# Chip.net
KiCad netlist of a schematic drawn in Altium Designer
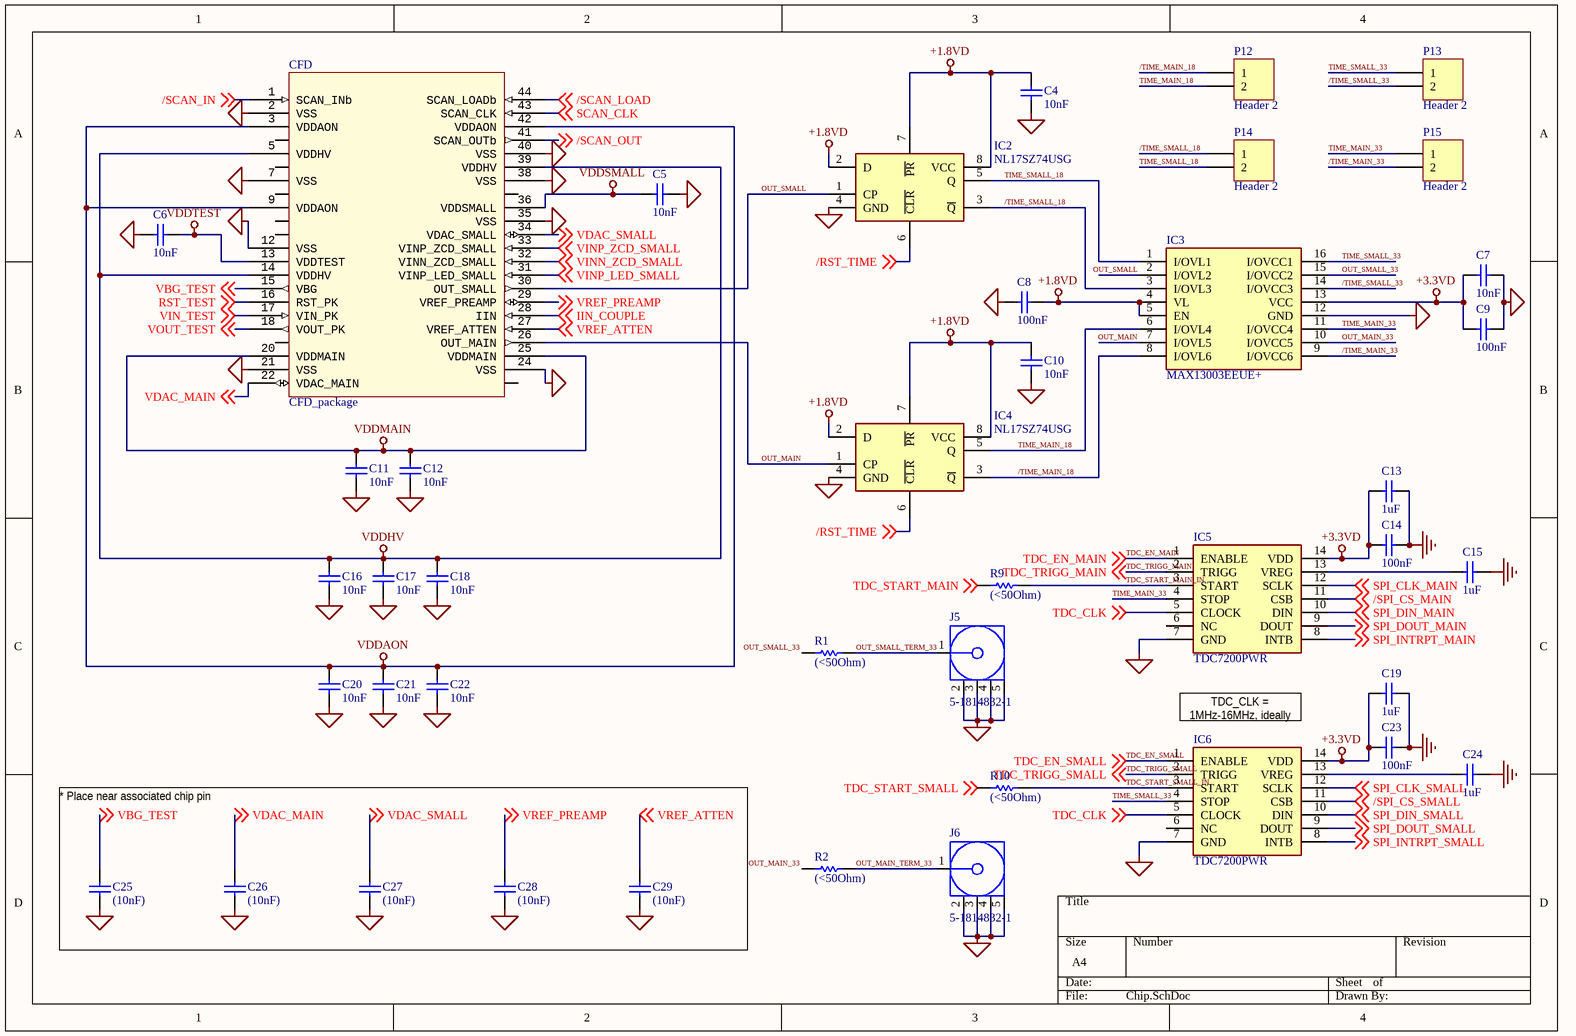
[diagram p0: Chip.SchDoc]

(export (version "E")
  (design (tool "Eeschema 10.0.6"))
  (components
    (comp (ref "C4")
      (value "10nF")
      (footprint "CAPC1608X90X35ML10T15")
      (description "0603")
      (fields (field (name "MANUFACTURER") "Murata"))
      (libsource (lib "Altium Content Vault") (part "CAP-NP-2"))
    )
    (comp (ref "C5")
      (value "10nF")
      (footprint "CAPC1608X90X35ML10T15")
      (description "0603")
      (fields (field (name "MANUFACTURER") "Murata"))
      (libsource (lib "Altium Content Vault") (part "CAP-NP-2"))
    )
    (comp (ref "C6")
      (value "10nF")
      (footprint "CAPC1608X90X35ML10T15")
      (description "0603")
      (fields (field (name "MANUFACTURER") "Murata"))
      (libsource (lib "Altium Content Vault") (part "CAP-NP-2"))
    )
    (comp (ref "C7")
      (value "10nF")
      (footprint "CAPC1608X90X35ML10T15")
      (description "0603")
      (fields (field (name "MANUFACTURER") "Murata"))
      (libsource (lib "Altium Content Vault") (part "CAP-NP-2"))
    )
    (comp (ref "C8")
      (value "100nF")
      (footprint "CAPC1608X90X35ML10T15")
      (description "0603")
      (fields (field (name "MANUFACTURER") "Murata"))
      (libsource (lib "Altium Content Vault") (part "CAP-NP-2"))
    )
    (comp (ref "C9")
      (value "100nF")
      (footprint "CAPC1608X90X35ML10T15")
      (description "0603")
      (fields (field (name "MANUFACTURER") "Murata"))
      (libsource (lib "Altium Content Vault") (part "CAP-NP-2"))
    )
    (comp (ref "C10")
      (value "10nF")
      (footprint "CAPC1608X90X35ML10T15")
      (description "0603")
      (fields (field (name "MANUFACTURER") "Murata"))
      (libsource (lib "Altium Content Vault") (part "CAP-NP-2"))
    )
    (comp (ref "C11")
      (value "10nF")
      (footprint "CAPC1608X90X35ML10T15")
      (description "0603")
      (fields (field (name "MANUFACTURER") "Murata"))
      (libsource (lib "Altium Content Vault") (part "CAP-NP-2"))
    )
    (comp (ref "C12")
      (value "10nF")
      (footprint "CAPC1608X90X35ML10T15")
      (description "0603")
      (fields (field (name "MANUFACTURER") "Murata"))
      (libsource (lib "Altium Content Vault") (part "CAP-NP-2"))
    )
    (comp (ref "C13")
      (value "1uF")
      (footprint "CAPC1608X90X35ML10T15")
      (description "0603")
      (fields (field (name "MANUFACTURER") "Murata"))
      (libsource (lib "Altium Content Vault") (part "CAP-NP-2"))
    )
    (comp (ref "C14")
      (value "100nF")
      (footprint "CAPC1608X90X35ML10T15")
      (description "0603")
      (fields (field (name "MANUFACTURER") "Murata"))
      (libsource (lib "Altium Content Vault") (part "CAP-NP-2"))
    )
    (comp (ref "C15")
      (value "1uF")
      (footprint "CAPC1608X90X35ML10T15")
      (description "0603")
      (fields (field (name "MANUFACTURER") "Murata"))
      (libsource (lib "Altium Content Vault") (part "CAP-NP-2"))
    )
    (comp (ref "C16")
      (value "10nF")
      (footprint "CAPC1608X90X35ML10T15")
      (description "0603")
      (fields (field (name "MANUFACTURER") "Murata"))
      (libsource (lib "Altium Content Vault") (part "CAP-NP-2"))
    )
    (comp (ref "C17")
      (value "10nF")
      (footprint "CAPC1608X90X35ML10T15")
      (description "0603")
      (fields (field (name "MANUFACTURER") "Murata"))
      (libsource (lib "Altium Content Vault") (part "CAP-NP-2"))
    )
    (comp (ref "C18")
      (value "10nF")
      (footprint "CAPC1608X90X35ML10T15")
      (description "0603")
      (fields (field (name "MANUFACTURER") "Murata"))
      (libsource (lib "Altium Content Vault") (part "CAP-NP-2"))
    )
    (comp (ref "C19")
      (value "1uF")
      (footprint "CAPC1608X90X35ML10T15")
      (description "0603")
      (fields (field (name "MANUFACTURER") "Murata"))
      (libsource (lib "Altium Content Vault") (part "CAP-NP-2"))
    )
    (comp (ref "C20")
      (value "10nF")
      (footprint "CAPC1608X90X35ML10T15")
      (description "0603")
      (fields (field (name "MANUFACTURER") "Murata"))
      (libsource (lib "Altium Content Vault") (part "CAP-NP-2"))
    )
    (comp (ref "C21")
      (value "10nF")
      (footprint "CAPC1608X90X35ML10T15")
      (description "0603")
      (fields (field (name "MANUFACTURER") "Murata"))
      (libsource (lib "Altium Content Vault") (part "CAP-NP-2"))
    )
    (comp (ref "C22")
      (value "10nF")
      (footprint "CAPC1608X90X35ML10T15")
      (description "0603")
      (fields (field (name "MANUFACTURER") "Murata"))
      (libsource (lib "Altium Content Vault") (part "CAP-NP-2"))
    )
    (comp (ref "C23")
      (value "100nF")
      (footprint "CAPC1608X90X35ML10T15")
      (description "0603")
      (fields (field (name "MANUFACTURER") "Murata"))
      (libsource (lib "Altium Content Vault") (part "CAP-NP-2"))
    )
    (comp (ref "C24")
      (value "1uF")
      (footprint "CAPC1608X90X35ML10T15")
      (description "0603")
      (fields (field (name "MANUFACTURER") "Murata"))
      (libsource (lib "Altium Content Vault") (part "CAP-NP-2"))
    )
    (comp (ref "C25")
      (value "(10nF)")
      (footprint "CAPC1608X90X35ML10T15")
      (description "0603")
      (fields (field (name "MANUFACTURER") "Murata"))
      (libsource (lib "Altium Content Vault") (part "CAP-NP-2"))
    )
    (comp (ref "C26")
      (value "(10nF)")
      (footprint "CAPC1608X90X35ML10T15")
      (description "0603")
      (fields (field (name "MANUFACTURER") "Murata"))
      (libsource (lib "Altium Content Vault") (part "CAP-NP-2"))
    )
    (comp (ref "C27")
      (value "(10nF)")
      (footprint "CAPC1608X90X35ML10T15")
      (description "0603")
      (fields (field (name "MANUFACTURER") "Murata"))
      (libsource (lib "Altium Content Vault") (part "CAP-NP-2"))
    )
    (comp (ref "C28")
      (value "(10nF)")
      (footprint "CAPC1608X90X35ML10T15")
      (description "0603")
      (fields (field (name "MANUFACTURER") "Murata"))
      (libsource (lib "Altium Content Vault") (part "CAP-NP-2"))
    )
    (comp (ref "C29")
      (value "(10nF)")
      (footprint "CAPC1608X90X35ML10T15")
      (description "0603")
      (fields (field (name "MANUFACTURER") "Murata"))
      (libsource (lib "Altium Content Vault") (part "CAP-NP-2"))
    )
    (comp (ref "CFD")
      (value "CFD_package")
      (footprint "QFN50P700X700X80_HS-45N_WIDEVIAS")
      (libsource (lib "intlib") (part "CFD_package"))
    )
    (comp (ref "IC2")
      (value "NL17SZ74USG")
      (footprint "SamacSys:SOP50P310X90-8N")
      (description "Flip Flops 1.65-5.5V CMOS Single D-Type")
      (libsource (lib "SamacSys") (part "NL17SZ74USG"))
    )
    (comp (ref "IC3")
      (value "MAX13003EEUE+")
      (footprint "SamacSys:SOP65P640X110-16N")
      (description "Integrated Circuit")
      (libsource (lib "*") (part "MAX13003EEUE+"))
    )
    (comp (ref "IC4")
      (value "NL17SZ74USG")
      (footprint "SamacSys:SOP50P310X90-8N")
      (description "Flip Flops 1.65-5.5V CMOS Single D-Type")
      (libsource (lib "SamacSys") (part "NL17SZ74USG"))
    )
    (comp (ref "IC5")
      (value "TDC7200PWR")
      (footprint "SamacSys:SOP65P640X120-14N")
      (description "Integrated Circuit")
      (libsource (lib "*") (part "TDC7200PWR"))
    )
    (comp (ref "IC6")
      (value "TDC7200PWR")
      (footprint "SamacSys:SOP65P640X120-14N")
      (description "Integrated Circuit")
      (libsource (lib "*") (part "TDC7200PWR"))
    )
    (comp (ref "J5")
      (value "5-1814832-1")
      (footprint "TECO-5-1814832-1_V")
      (fields (field (name "MANUFACTURER") "TE Connectivity"))
      (libsource (lib "Altium Content Vault") (part "CN-S-4F-RF5"))
    )
    (comp (ref "J6")
      (value "5-1814832-1")
      (footprint "TECO-5-1814832-1_V")
      (fields (field (name "MANUFACTURER") "TE Connectivity"))
      (libsource (lib "Altium Content Vault") (part "CN-S-4F-RF5"))
    )
    (comp (ref "P12")
      (value "Header 2")
      (footprint "HDR1X2")
      (description "Header, 2-Pin")
      (fields (field (name "PUBLISHER") "Altium Limited"))
      (libsource (lib "Miscellaneous Connectors") (part "Header 2"))
    )
    (comp (ref "P13")
      (value "Header 2")
      (footprint "HDR1X2")
      (description "Header, 2-Pin")
      (fields (field (name "PUBLISHER") "Altium Limited"))
      (libsource (lib "Miscellaneous Connectors") (part "Header 2"))
    )
    (comp (ref "P14")
      (value "Header 2")
      (footprint "HDR1X2")
      (description "Header, 2-Pin")
      (fields (field (name "PUBLISHER") "Altium Limited"))
      (libsource (lib "Miscellaneous Connectors") (part "Header 2"))
    )
    (comp (ref "P15")
      (value "Header 2")
      (footprint "HDR1X2")
      (description "Header, 2-Pin")
      (fields (field (name "PUBLISHER") "Altium Limited"))
      (libsource (lib "Miscellaneous Connectors") (part "Header 2"))
    )
    (comp (ref "R1")
      (value "(<50Ohm)")
      (footprint "RESC1609X50X30NL8T20")
      (description "0603")
      (fields (field (name "MANUFACTURER") "Vishay Semiconductor"))
      (libsource (lib "Altium Content Vault") (part "RES-2"))
    )
    (comp (ref "R2")
      (value "(<50Ohm)")
      (footprint "RESC1609X50X30NL8T20")
      (description "0603")
      (fields (field (name "MANUFACTURER") "Vishay Semiconductor"))
      (libsource (lib "Altium Content Vault") (part "RES-2"))
    )
    (comp (ref "R9")
      (value "(<50Ohm)")
      (footprint "RESC1609X50X30NL8T20")
      (description "0603")
      (fields (field (name "MANUFACTURER") "Vishay Semiconductor"))
      (libsource (lib "Altium Content Vault") (part "RES-2"))
    )
    (comp (ref "R10")
      (value "(<50Ohm)")
      (footprint "RESC1609X50X30NL8T20")
      (description "0603")
      (fields (field (name "MANUFACTURER") "Vishay Semiconductor"))
      (libsource (lib "Altium Content Vault") (part "RES-2"))
    )
  )
  (nets
    (net (code "1") (name "+1.8VD") (class "Default")
      (node (ref "C10") (pin "2") (pinfunction "2_2") (pintype "passive"))
      (node (ref "C4") (pin "2") (pinfunction "2_2") (pintype "passive"))
      (node (ref "C8") (pin "2") (pinfunction "2_2") (pintype "passive"))
      (node (ref "IC2") (pin "2") (pinfunction "D_2") (pintype "passive"))
      (node (ref "IC2") (pin "7") (pinfunction "~{PR}_7") (pintype "passive"))
      (node (ref "IC2") (pin "8") (pinfunction "VCC_8") (pintype "passive"))
      (node (ref "IC3") (pin "4") (pinfunction "VL_4") (pintype "passive"))
      (node (ref "IC3") (pin "5") (pinfunction "EN_5") (pintype "passive"))
      (node (ref "IC4") (pin "2") (pinfunction "D_2") (pintype "passive"))
      (node (ref "IC4") (pin "7") (pinfunction "~{PR}_7") (pintype "passive"))
      (node (ref "IC4") (pin "8") (pinfunction "VCC_8") (pintype "passive"))
    )
    (net (code "2") (name "+3.3VD") (class "Default")
      (node (ref "C13") (pin "1") (pinfunction "1_1") (pintype "passive"))
      (node (ref "C14") (pin "1") (pinfunction "1_1") (pintype "passive"))
      (node (ref "C19") (pin "1") (pinfunction "1_1") (pintype "passive"))
      (node (ref "C23") (pin "1") (pinfunction "1_1") (pintype "passive"))
      (node (ref "C7") (pin "2") (pinfunction "2_2") (pintype "passive"))
      (node (ref "C9") (pin "2") (pinfunction "2_2") (pintype "passive"))
      (node (ref "IC3") (pin "13") (pinfunction "VCC_13") (pintype "passive"))
      (node (ref "IC5") (pin "14") (pinfunction "VDD_14") (pintype "passive"))
      (node (ref "IC6") (pin "14") (pinfunction "VDD_14") (pintype "passive"))
    )
    (net (code "3") (name "/OUT_MAIN") (class "Default")
      (node (ref "CFD") (pin "26") (pinfunction "OUT_MAIN_26") (pintype "output"))
      (node (ref "IC3") (pin "7") (pinfunction "I/OVL5_7") (pintype "passive"))
      (node (ref "IC4") (pin "1") (pinfunction "CP_1") (pintype "passive"))
    )
    (net (code "4") (name "/OUT_MAIN_33") (class "Default")
      (node (ref "IC3") (pin "10") (pinfunction "I/OVCC5_10") (pintype "passive"))
      (node (ref "R2") (pin "2") (pinfunction "2_2") (pintype "passive"))
    )
    (net (code "5") (name "/OUT_MAIN_TERM_33") (class "Default")
      (node (ref "J6") (pin "1") (pinfunction "1_1") (pintype "passive"))
      (node (ref "R2") (pin "1") (pinfunction "1_1") (pintype "passive"))
    )
    (net (code "6") (name "/OUT_SMALL") (class "Default")
      (node (ref "CFD") (pin "30") (pinfunction "OUT_SMALL_30") (pintype "output"))
      (node (ref "IC2") (pin "1") (pinfunction "CP_1") (pintype "passive"))
      (node (ref "IC3") (pin "2") (pinfunction "I/OVL2_2") (pintype "passive"))
    )
    (net (code "7") (name "/OUT_SMALL_33") (class "Default")
      (node (ref "IC3") (pin "15") (pinfunction "I/OVCC2_15") (pintype "passive"))
      (node (ref "R1") (pin "2") (pinfunction "2_2") (pintype "passive"))
    )
    (net (code "8") (name "/OUT_SMALL_TERM_33") (class "Default")
      (node (ref "J5") (pin "1") (pinfunction "1_1") (pintype "passive"))
      (node (ref "R1") (pin "1") (pinfunction "1_1") (pintype "passive"))
    )
    (net (code "9") (name "/TDC_START_MAIN_IN") (class "Default")
      (node (ref "IC5") (pin "3") (pinfunction "START_3") (pintype "passive"))
      (node (ref "R9") (pin "1") (pinfunction "1_1") (pintype "passive"))
    )
    (net (code "10") (name "/TDC_START_SMALL_IN") (class "Default")
      (node (ref "IC6") (pin "3") (pinfunction "START_3") (pintype "passive"))
      (node (ref "R10") (pin "1") (pinfunction "1_1") (pintype "passive"))
    )
    (net (code "11") (name "/TIME_MAIN_18") (class "Default")
      (node (ref "IC3") (pin "6") (pinfunction "I/OVL4_6") (pintype "passive"))
      (node (ref "IC4") (pin "5") (pinfunction "Q_5") (pintype "passive"))
      (node (ref "P12") (pin "2") (pinfunction "2_2") (pintype "passive"))
    )
    (net (code "12") (name "/TIME_MAIN_33") (class "Default")
      (node (ref "IC3") (pin "11") (pinfunction "I/OVCC4_11") (pintype "passive"))
      (node (ref "IC5") (pin "4") (pinfunction "STOP_4") (pintype "passive"))
      (node (ref "P15") (pin "1") (pinfunction "1_1") (pintype "passive"))
    )
    (net (code "13") (name "/TIME_SMALL_18") (class "Default")
      (node (ref "IC2") (pin "5") (pinfunction "Q_5") (pintype "passive"))
      (node (ref "IC3") (pin "1") (pinfunction "I/OVL1_1") (pintype "passive"))
      (node (ref "P14") (pin "2") (pinfunction "2_2") (pintype "passive"))
    )
    (net (code "14") (name "/TIME_SMALL_33") (class "Default")
      (node (ref "IC3") (pin "16") (pinfunction "I/OVCC1_16") (pintype "passive"))
      (node (ref "IC6") (pin "4") (pinfunction "STOP_4") (pintype "passive"))
      (node (ref "P13") (pin "1") (pinfunction "1_1") (pintype "passive"))
    )
    (net (code "15") (name "/{slash}TIME_MAIN_18") (class "Default")
      (node (ref "IC3") (pin "8") (pinfunction "I/OVL6_8") (pintype "passive"))
      (node (ref "IC4") (pin "3") (pinfunction "~{Q}_3") (pintype "passive"))
      (node (ref "P12") (pin "1") (pinfunction "1_1") (pintype "passive"))
    )
    (net (code "16") (name "/{slash}TIME_MAIN_33") (class "Default")
      (node (ref "IC3") (pin "9") (pinfunction "I/OVCC6_9") (pintype "passive"))
      (node (ref "P15") (pin "2") (pinfunction "2_2") (pintype "passive"))
    )
    (net (code "17") (name "/{slash}TIME_SMALL_18") (class "Default")
      (node (ref "IC2") (pin "3") (pinfunction "~{Q}_3") (pintype "passive"))
      (node (ref "IC3") (pin "3") (pinfunction "I/OVL3_3") (pintype "passive"))
      (node (ref "P14") (pin "1") (pinfunction "1_1") (pintype "passive"))
    )
    (net (code "18") (name "/{slash}TIME_SMALL_33") (class "Default")
      (node (ref "IC3") (pin "14") (pinfunction "I/OVCC3_14") (pintype "passive"))
      (node (ref "P13") (pin "2") (pinfunction "2_2") (pintype "passive"))
    )
    (net (code "19") (name "GND") (class "Default")
      (node (ref "C10") (pin "1") (pinfunction "1_1") (pintype "passive"))
      (node (ref "C11") (pin "1") (pinfunction "1_1") (pintype "passive"))
      (node (ref "C12") (pin "1") (pinfunction "1_1") (pintype "passive"))
      (node (ref "C13") (pin "2") (pinfunction "2_2") (pintype "passive"))
      (node (ref "C14") (pin "2") (pinfunction "2_2") (pintype "passive"))
      (node (ref "C15") (pin "2") (pinfunction "2_2") (pintype "passive"))
      (node (ref "C16") (pin "1") (pinfunction "1_1") (pintype "passive"))
      (node (ref "C17") (pin "1") (pinfunction "1_1") (pintype "passive"))
      (node (ref "C18") (pin "1") (pinfunction "1_1") (pintype "passive"))
      (node (ref "C19") (pin "2") (pinfunction "2_2") (pintype "passive"))
      (node (ref "C20") (pin "1") (pinfunction "1_1") (pintype "passive"))
      (node (ref "C21") (pin "1") (pinfunction "1_1") (pintype "passive"))
      (node (ref "C22") (pin "1") (pinfunction "1_1") (pintype "passive"))
      (node (ref "C23") (pin "2") (pinfunction "2_2") (pintype "passive"))
      (node (ref "C24") (pin "2") (pinfunction "2_2") (pintype "passive"))
      (node (ref "C25") (pin "1") (pinfunction "1_1") (pintype "passive"))
      (node (ref "C26") (pin "1") (pinfunction "1_1") (pintype "passive"))
      (node (ref "C27") (pin "1") (pinfunction "1_1") (pintype "passive"))
      (node (ref "C28") (pin "1") (pinfunction "1_1") (pintype "passive"))
      (node (ref "C29") (pin "1") (pinfunction "1_1") (pintype "passive"))
      (node (ref "C4") (pin "1") (pinfunction "1_1") (pintype "passive"))
      (node (ref "C5") (pin "1") (pinfunction "1_1") (pintype "passive"))
      (node (ref "C6") (pin "2") (pinfunction "2_2") (pintype "passive"))
      (node (ref "C7") (pin "1") (pinfunction "1_1") (pintype "passive"))
      (node (ref "C8") (pin "1") (pinfunction "1_1") (pintype "passive"))
      (node (ref "C9") (pin "1") (pinfunction "1_1") (pintype "passive"))
      (node (ref "CFD") (pin "12") (pinfunction "VSS_12") (pintype "power_in"))
      (node (ref "CFD") (pin "2") (pinfunction "VSS_2") (pintype "power_in"))
      (node (ref "CFD") (pin "21") (pinfunction "VSS_21") (pintype "power_in"))
      (node (ref "CFD") (pin "24") (pinfunction "VSS_24") (pintype "power_in"))
      (node (ref "CFD") (pin "35") (pinfunction "VSS_35") (pintype "power_in"))
      (node (ref "CFD") (pin "38") (pinfunction "VSS_38") (pintype "power_in"))
      (node (ref "CFD") (pin "40") (pinfunction "VSS_40") (pintype "power_in"))
      (node (ref "CFD") (pin "7") (pinfunction "VSS_7") (pintype "power_in"))
      (node (ref "IC2") (pin "4") (pinfunction "GND_4") (pintype "passive"))
      (node (ref "IC3") (pin "12") (pinfunction "GND_12") (pintype "passive"))
      (node (ref "IC4") (pin "4") (pinfunction "GND_4") (pintype "passive"))
      (node (ref "IC5") (pin "7") (pinfunction "GND_7") (pintype "passive"))
      (node (ref "IC6") (pin "7") (pinfunction "GND_7") (pintype "passive"))
      (node (ref "J5") (pin "2") (pinfunction "2_2") (pintype "passive"))
      (node (ref "J5") (pin "3") (pinfunction "3_3") (pintype "passive"))
      (node (ref "J5") (pin "4") (pinfunction "4_4") (pintype "passive"))
      (node (ref "J5") (pin "5") (pinfunction "5_5") (pintype "passive"))
      (node (ref "J6") (pin "2") (pinfunction "2_2") (pintype "passive"))
      (node (ref "J6") (pin "3") (pinfunction "3_3") (pintype "passive"))
      (node (ref "J6") (pin "4") (pinfunction "4_4") (pintype "passive"))
      (node (ref "J6") (pin "5") (pinfunction "5_5") (pintype "passive"))
    )
    (net (code "20") (name "IIN_COUPLE") (class "Default")
      (node (ref "CFD") (pin "28") (pinfunction "IIN_28") (pintype "input"))
    )
    (net (code "21") (name "Net-(IC5-VREG)") (class "Default")
      (node (ref "C15") (pin "1") (pinfunction "1_1") (pintype "passive"))
      (node (ref "IC5") (pin "13") (pinfunction "VREG_13") (pintype "passive"))
    )
    (net (code "22") (name "Net-(IC6-VREG)") (class "Default")
      (node (ref "C24") (pin "1") (pinfunction "1_1") (pintype "passive"))
      (node (ref "IC6") (pin "13") (pinfunction "VREG_13") (pintype "passive"))
    )
    (net (code "23") (name "RST_TEST") (class "Default")
      (node (ref "CFD") (pin "16") (pinfunction "RST_PK_16") (pintype "passive"))
    )
    (net (code "24") (name "SCAN_CLK") (class "Default")
      (node (ref "CFD") (pin "43") (pinfunction "SCAN_CLK_43") (pintype "input"))
    )
    (net (code "25") (name "SPI_CLK_MAIN") (class "Default")
      (node (ref "IC5") (pin "12") (pinfunction "SCLK_12") (pintype "passive"))
    )
    (net (code "26") (name "SPI_CLK_SMALL") (class "Default")
      (node (ref "IC6") (pin "12") (pinfunction "SCLK_12") (pintype "passive"))
    )
    (net (code "27") (name "SPI_DIN_MAIN") (class "Default")
      (node (ref "IC5") (pin "10") (pinfunction "DIN_10") (pintype "passive"))
    )
    (net (code "28") (name "SPI_DIN_SMALL") (class "Default")
      (node (ref "IC6") (pin "10") (pinfunction "DIN_10") (pintype "passive"))
    )
    (net (code "29") (name "SPI_DOUT_MAIN") (class "Default")
      (node (ref "IC5") (pin "9") (pinfunction "DOUT_9") (pintype "passive"))
    )
    (net (code "30") (name "SPI_DOUT_SMALL") (class "Default")
      (node (ref "IC6") (pin "9") (pinfunction "DOUT_9") (pintype "passive"))
    )
    (net (code "31") (name "SPI_INTRPT_MAIN") (class "Default")
      (node (ref "IC5") (pin "8") (pinfunction "INTB_8") (pintype "passive"))
    )
    (net (code "32") (name "SPI_INTRPT_SMALL") (class "Default")
      (node (ref "IC6") (pin "8") (pinfunction "INTB_8") (pintype "passive"))
    )
    (net (code "33") (name "TDC_CLK") (class "Default")
      (node (ref "IC5") (pin "5") (pinfunction "CLOCK_5") (pintype "passive"))
      (node (ref "IC6") (pin "5") (pinfunction "CLOCK_5") (pintype "passive"))
    )
    (net (code "34") (name "TDC_EN_MAIN") (class "Default")
      (node (ref "IC5") (pin "1") (pinfunction "ENABLE_1") (pintype "passive"))
    )
    (net (code "35") (name "TDC_EN_SMALL") (class "Default")
      (node (ref "IC6") (pin "1") (pinfunction "ENABLE_1") (pintype "passive"))
    )
    (net (code "36") (name "TDC_START_MAIN") (class "Default")
      (node (ref "R9") (pin "2") (pinfunction "2_2") (pintype "passive"))
    )
    (net (code "37") (name "TDC_START_SMALL") (class "Default")
      (node (ref "R10") (pin "2") (pinfunction "2_2") (pintype "passive"))
    )
    (net (code "38") (name "TDC_TRIGG_MAIN") (class "Default")
      (node (ref "IC5") (pin "2") (pinfunction "TRIGG_2") (pintype "passive"))
    )
    (net (code "39") (name "TDC_TRIGG_SMALL") (class "Default")
      (node (ref "IC6") (pin "2") (pinfunction "TRIGG_2") (pintype "passive"))
    )
    (net (code "40") (name "VBG_TEST") (class "Default")
      (node (ref "C25") (pin "2") (pinfunction "2_2") (pintype "passive"))
      (node (ref "CFD") (pin "15") (pinfunction "VBG_15") (pintype "output"))
    )
    (net (code "41") (name "VDAC_MAIN") (class "Default")
      (node (ref "C26") (pin "2") (pinfunction "2_2") (pintype "passive"))
      (node (ref "CFD") (pin "22") (pinfunction "VDAC_MAIN_22") (pintype "bidirectional"))
    )
    (net (code "42") (name "VDAC_SMALL") (class "Default")
      (node (ref "C27") (pin "2") (pinfunction "2_2") (pintype "passive"))
      (node (ref "CFD") (pin "34") (pinfunction "VDAC_SMALL_34") (pintype "bidirectional"))
    )
    (net (code "43") (name "VDDAON") (class "Default")
      (node (ref "C20") (pin "2") (pinfunction "2_2") (pintype "passive"))
      (node (ref "C21") (pin "2") (pinfunction "2_2") (pintype "passive"))
      (node (ref "C22") (pin "2") (pinfunction "2_2") (pintype "passive"))
      (node (ref "CFD") (pin "3") (pinfunction "VDDAON_3") (pintype "power_in"))
      (node (ref "CFD") (pin "42") (pinfunction "VDDAON_42") (pintype "power_in"))
      (node (ref "CFD") (pin "9") (pinfunction "VDDAON_9") (pintype "power_in"))
    )
    (net (code "44") (name "VDDHV") (class "Default")
      (node (ref "C16") (pin "2") (pinfunction "2_2") (pintype "passive"))
      (node (ref "C17") (pin "2") (pinfunction "2_2") (pintype "passive"))
      (node (ref "C18") (pin "2") (pinfunction "2_2") (pintype "passive"))
      (node (ref "CFD") (pin "14") (pinfunction "VDDHV_14") (pintype "power_in"))
      (node (ref "CFD") (pin "39") (pinfunction "VDDHV_39") (pintype "power_in"))
      (node (ref "CFD") (pin "5") (pinfunction "VDDHV_5") (pintype "power_in"))
    )
    (net (code "45") (name "VDDMAIN") (class "Default")
      (node (ref "C11") (pin "2") (pinfunction "2_2") (pintype "passive"))
      (node (ref "C12") (pin "2") (pinfunction "2_2") (pintype "passive"))
      (node (ref "CFD") (pin "20") (pinfunction "VDDMAIN_20") (pintype "power_in"))
      (node (ref "CFD") (pin "25") (pinfunction "VDDMAIN_25") (pintype "power_in"))
    )
    (net (code "46") (name "VDDSMALL") (class "Default")
      (node (ref "C5") (pin "2") (pinfunction "2_2") (pintype "passive"))
      (node (ref "CFD") (pin "36") (pinfunction "VDDSMALL_36") (pintype "power_in"))
    )
    (net (code "47") (name "VDDTEST") (class "Default")
      (node (ref "C6") (pin "1") (pinfunction "1_1") (pintype "passive"))
      (node (ref "CFD") (pin "13") (pinfunction "VDDTEST_13") (pintype "power_in"))
    )
    (net (code "48") (name "VINN_ZCD_SMALL") (class "Default")
      (node (ref "CFD") (pin "32") (pinfunction "VINN_ZCD_SMALL_32") (pintype "input"))
    )
    (net (code "49") (name "VINP_LED_SMALL") (class "Default")
      (node (ref "CFD") (pin "31") (pinfunction "VINP_LED_SMALL_31") (pintype "input"))
    )
    (net (code "50") (name "VINP_ZCD_SMALL") (class "Default")
      (node (ref "CFD") (pin "33") (pinfunction "VINP_ZCD_SMALL_33") (pintype "input"))
    )
    (net (code "51") (name "VIN_TEST") (class "Default")
      (node (ref "CFD") (pin "17") (pinfunction "VIN_PK_17") (pintype "input"))
    )
    (net (code "52") (name "VOUT_TEST") (class "Default")
      (node (ref "CFD") (pin "18") (pinfunction "VOUT_PK_18") (pintype "output"))
    )
    (net (code "53") (name "VREF_ATTEN") (class "Default")
      (node (ref "C29") (pin "2") (pinfunction "2_2") (pintype "passive"))
      (node (ref "CFD") (pin "27") (pinfunction "VREF_ATTEN_27") (pintype "input"))
    )
    (net (code "54") (name "VREF_PREAMP") (class "Default")
      (node (ref "C28") (pin "2") (pinfunction "2_2") (pintype "passive"))
      (node (ref "CFD") (pin "29") (pinfunction "VREF_PREAMP_29") (pintype "bidirectional"))
    )
    (net (code "55") (name "unconnected-(CFD-Pad4)") (class "Default")
      (node (ref "CFD") (pin "4") (pintype "tri_state"))
    )
    (net (code "56") (name "unconnected-(CFD-Pad6)") (class "Default")
      (node (ref "CFD") (pin "6") (pintype "tri_state"))
    )
    (net (code "57") (name "unconnected-(CFD-Pad8)") (class "Default")
      (node (ref "CFD") (pin "8") (pintype "tri_state"))
    )
    (net (code "58") (name "unconnected-(CFD-Pad10)") (class "Default")
      (node (ref "CFD") (pin "10") (pintype "tri_state"))
    )
    (net (code "59") (name "unconnected-(CFD-Pad11)") (class "Default")
      (node (ref "CFD") (pin "11") (pintype "tri_state"))
    )
    (net (code "60") (name "unconnected-(CFD-Pad19)") (class "Default")
      (node (ref "CFD") (pin "19") (pintype "tri_state"))
    )
    (net (code "61") (name "unconnected-(CFD-Pad23)") (class "Default")
      (node (ref "CFD") (pin "23") (pintype "tri_state"))
    )
    (net (code "62") (name "unconnected-(CFD-Pad37)") (class "Default")
      (node (ref "CFD") (pin "37") (pintype "tri_state"))
    )
    (net (code "63") (name "unconnected-(IC5-NC-Pad6)") (class "Default")
      (node (ref "IC5") (pin "6") (pinfunction "NC_6") (pintype "passive"))
    )
    (net (code "64") (name "unconnected-(IC6-NC-Pad6)") (class "Default")
      (node (ref "IC6") (pin "6") (pinfunction "NC_6") (pintype "passive"))
    )
    (net (code "65") (name "{slash}RST_TIME") (class "Default")
      (node (ref "IC2") (pin "6") (pinfunction "~{CLR}_6") (pintype "passive"))
      (node (ref "IC4") (pin "6") (pinfunction "~{CLR}_6") (pintype "passive"))
    )
    (net (code "66") (name "{slash}SCAN_IN") (class "Default")
      (node (ref "CFD") (pin "1") (pinfunction "SCAN_INb_1") (pintype "input"))
    )
    (net (code "67") (name "{slash}SCAN_LOAD") (class "Default")
      (node (ref "CFD") (pin "44") (pinfunction "SCAN_LOADb_44") (pintype "input"))
    )
    (net (code "68") (name "{slash}SCAN_OUT") (class "Default")
      (node (ref "CFD") (pin "41") (pinfunction "SCAN_OUTb_41") (pintype "output"))
    )
    (net (code "69") (name "{slash}SPI_CS_MAIN") (class "Default")
      (node (ref "IC5") (pin "11") (pinfunction "CSB_11") (pintype "passive"))
    )
    (net (code "70") (name "{slash}SPI_CS_SMALL") (class "Default")
      (node (ref "IC6") (pin "11") (pinfunction "CSB_11") (pintype "passive"))
    )
  )
)
